# Measure_Select.net
KiCad netlist of a schematic drawn in Altium Designer
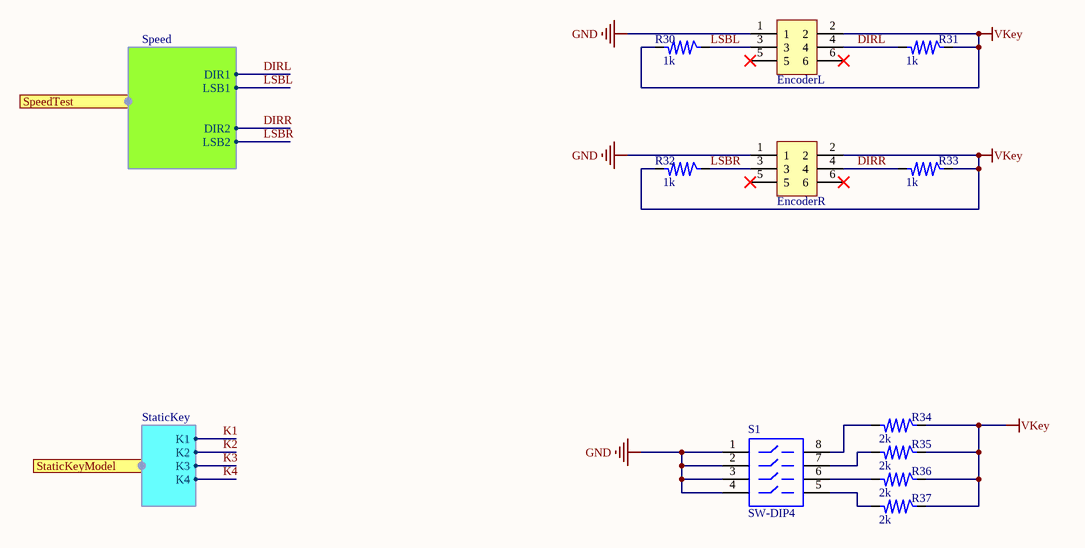
[diagram p0: Measure&Select.SchDoc]

(export (version "E")
  (design (tool "Eeschema 10.0.6"))
  (components
    (comp (ref "EncoderL") (value "编码器") (footprint "编码器") (libsource (lib "常用原件库") (part "编码器")))
    (comp (ref "EncoderR") (value "编码器") (footprint "编码器") (libsource (lib "常用原件库") (part "编码器")))
    (comp (ref "R30")
      (value "1k")
      (footprint "R0603")
      (description "电阻")
      (libsource (lib "LQ_Integrated_Library") (part "Resistor"))
    )
    (comp (ref "R31")
      (value "1k")
      (footprint "R0603")
      (description "电阻")
      (libsource (lib "LQ_Integrated_Library") (part "Resistor"))
    )
    (comp (ref "R32")
      (value "1k")
      (footprint "R0603")
      (description "电阻")
      (libsource (lib "LQ_Integrated_Library") (part "Resistor"))
    )
    (comp (ref "R33")
      (value "1k")
      (footprint "R0603")
      (description "电阻")
      (libsource (lib "LQ_Integrated_Library") (part "Resistor"))
    )
    (comp (ref "R34")
      (value "2k")
      (footprint "R0603")
      (description "电阻")
      (libsource (lib "LQ_Integrated_Library") (part "Resistor"))
    )
    (comp (ref "R35")
      (value "2k")
      (footprint "R0603")
      (description "电阻")
      (libsource (lib "LQ_Integrated_Library") (part "Resistor"))
    )
    (comp (ref "R36")
      (value "2k")
      (footprint "R0603")
      (description "电阻")
      (libsource (lib "LQ_Integrated_Library") (part "Resistor"))
    )
    (comp (ref "R37")
      (value "2k")
      (footprint "R0603")
      (description "电阻")
      (libsource (lib "LQ_Integrated_Library") (part "Resistor"))
    )
    (comp (ref "S1")
      (value "SW-DIP4")
      (footprint "SW-DIP4")
      (libsource (lib "LQ_Integrated_Library") (part "SW-DIP4"))
    )
  )
  (nets
    (net (code "3") (name "/DIRL") (class "Default")
      (node (ref "EncoderL") (pin "4") (pinfunction "4_4") (pintype "passive"))
      (node (ref "R31") (pin "1") (pinfunction "1_1") (pintype "passive"))
    )
    (net (code "4") (name "/DIRR") (class "Default")
      (node (ref "EncoderR") (pin "4") (pinfunction "4_4") (pintype "passive"))
      (node (ref "R33") (pin "1") (pinfunction "1_1") (pintype "passive"))
    )
    (net (code "9") (name "/LSBL") (class "Default")
      (node (ref "EncoderL") (pin "3") (pinfunction "3_3") (pintype "passive"))
      (node (ref "R30") (pin "2") (pinfunction "2_2") (pintype "passive"))
    )
    (net (code "10") (name "/LSBR") (class "Default")
      (node (ref "EncoderR") (pin "3") (pinfunction "3_3") (pintype "passive"))
      (node (ref "R32") (pin "2") (pinfunction "2_2") (pintype "passive"))
    )
    (net (code "13") (name "GND") (class "Default")
      (node (ref "EncoderL") (pin "1") (pinfunction "1_1") (pintype "passive"))
      (node (ref "EncoderR") (pin "1") (pinfunction "1_1") (pintype "passive"))
      (node (ref "S1") (pin "1") (pinfunction "1_1") (pintype "passive"))
      (node (ref "S1") (pin "2") (pinfunction "2_2") (pintype "passive"))
      (node (ref "S1") (pin "3") (pinfunction "3_3") (pintype "passive"))
      (node (ref "S1") (pin "4") (pinfunction "4_4") (pintype "passive"))
    )
    (net (code "14") (name "Net-(R34-Pad1)") (class "Default")
      (node (ref "R34") (pin "1") (pinfunction "1_1") (pintype "passive"))
      (node (ref "S1") (pin "8") (pinfunction "8_8") (pintype "passive"))
    )
    (net (code "15") (name "Net-(R35-Pad1)") (class "Default")
      (node (ref "R35") (pin "1") (pinfunction "1_1") (pintype "passive"))
      (node (ref "S1") (pin "7") (pinfunction "7_7") (pintype "passive"))
    )
    (net (code "16") (name "Net-(R36-Pad1)") (class "Default")
      (node (ref "R36") (pin "1") (pinfunction "1_1") (pintype "passive"))
      (node (ref "S1") (pin "6") (pinfunction "6_6") (pintype "passive"))
    )
    (net (code "17") (name "Net-(R37-Pad1)") (class "Default")
      (node (ref "R37") (pin "1") (pinfunction "1_1") (pintype "passive"))
      (node (ref "S1") (pin "5") (pinfunction "5_5") (pintype "passive"))
    )
    (net (code "18") (name "VKey") (class "Default")
      (node (ref "EncoderL") (pin "2") (pinfunction "2_2") (pintype "passive"))
      (node (ref "EncoderR") (pin "2") (pinfunction "2_2") (pintype "passive"))
      (node (ref "R30") (pin "1") (pinfunction "1_1") (pintype "passive"))
      (node (ref "R31") (pin "2") (pinfunction "2_2") (pintype "passive"))
      (node (ref "R32") (pin "1") (pinfunction "1_1") (pintype "passive"))
      (node (ref "R33") (pin "2") (pinfunction "2_2") (pintype "passive"))
      (node (ref "R34") (pin "2") (pinfunction "2_2") (pintype "passive"))
      (node (ref "R35") (pin "2") (pinfunction "2_2") (pintype "passive"))
      (node (ref "R36") (pin "2") (pinfunction "2_2") (pintype "passive"))
      (node (ref "R37") (pin "2") (pinfunction "2_2") (pintype "passive"))
    )
    (net (code "19") (name "unconnected-(EncoderL-Pad5)") (class "Default")
      (node (ref "EncoderL") (pin "5") (pinfunction "5_5") (pintype "passive+no_connect"))
    )
    (net (code "20") (name "unconnected-(EncoderL-Pad6)") (class "Default")
      (node (ref "EncoderL") (pin "6") (pinfunction "6_6") (pintype "passive+no_connect"))
    )
    (net (code "21") (name "unconnected-(EncoderR-Pad5)") (class "Default")
      (node (ref "EncoderR") (pin "5") (pinfunction "5_5") (pintype "passive+no_connect"))
    )
    (net (code "22") (name "unconnected-(EncoderR-Pad6)") (class "Default")
      (node (ref "EncoderR") (pin "6") (pinfunction "6_6") (pintype "passive+no_connect"))
    )
  )
)
